# Clock.net
KiCad netlist of a schematic drawn in Altium Designer
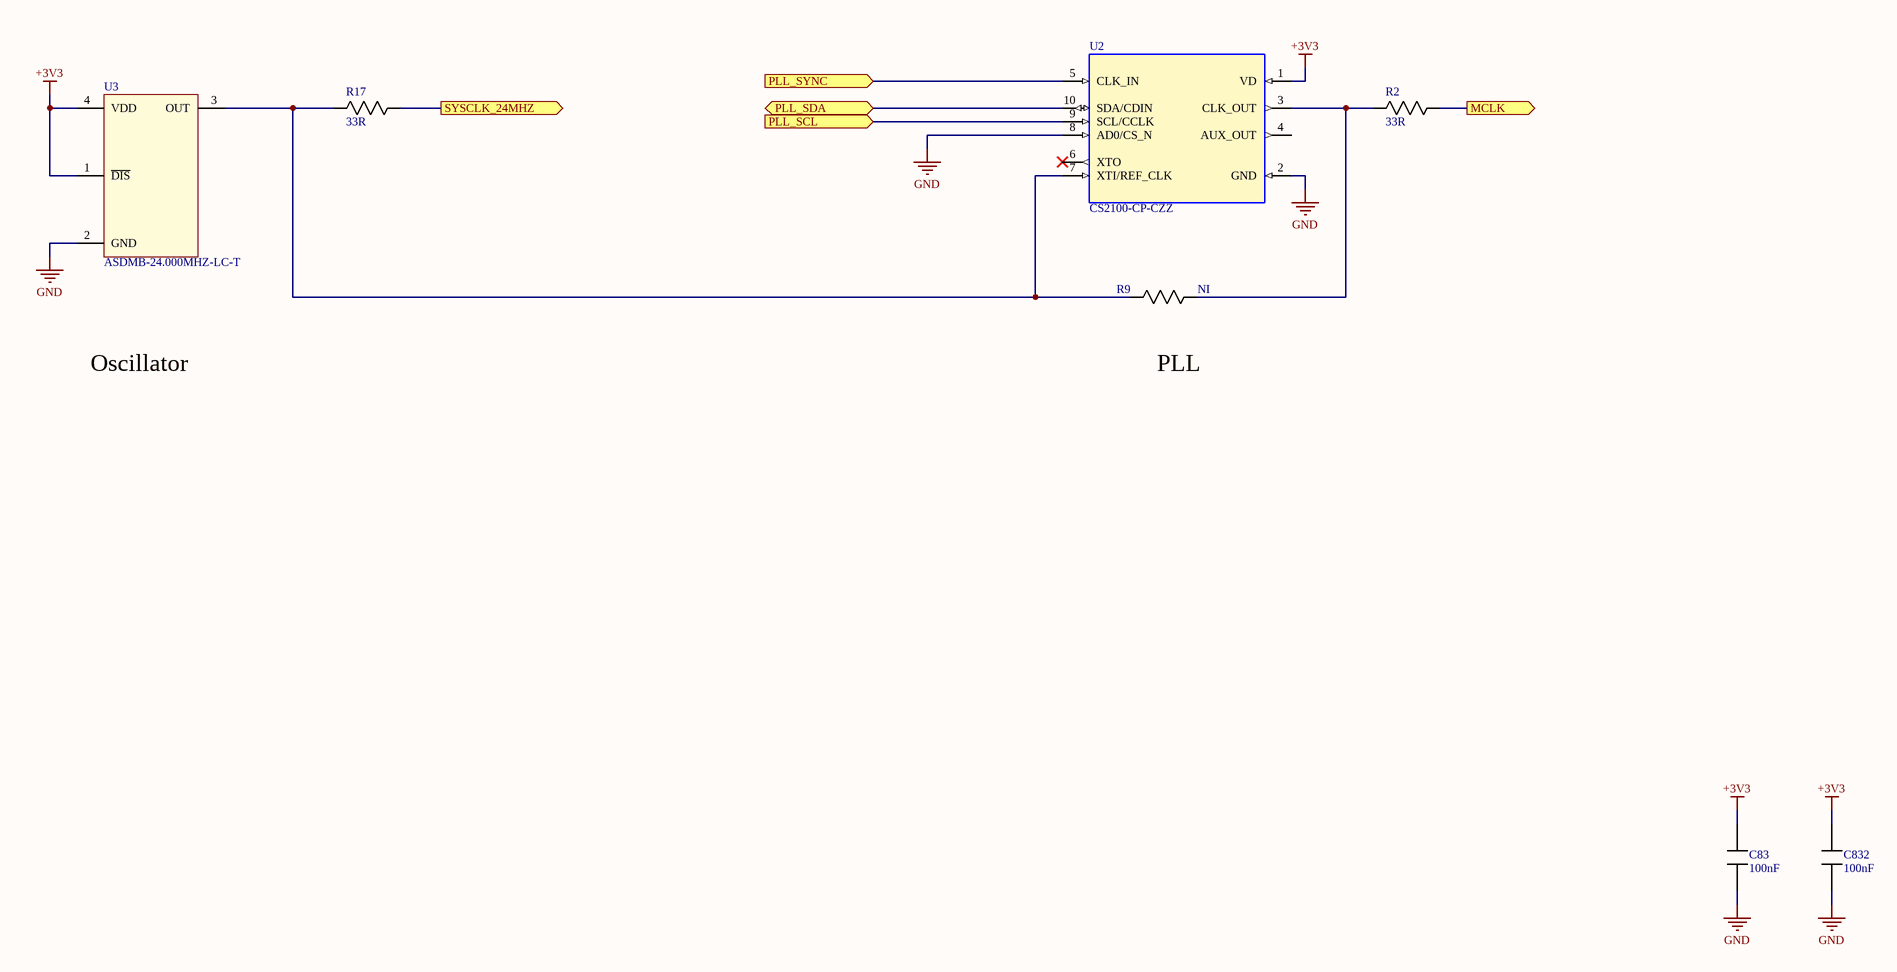
[diagram p0: Clock.SchDoc]

(export (version "E")
  (design (tool "Eeschema 10.0.6"))
  (components
    (comp (ref "C83")
      (value "100nF")
      (footprint "0603")
      (description "Capacitor")
      (fields (field (name "MFG") "Samsung"))
      (libsource (lib "INTER_2014") (part "Capacitor"))
    )
    (comp (ref "C832")
      (value "100nF")
      (footprint "0603")
      (description "Capacitor")
      (fields (field (name "MFG") "Samsung"))
      (libsource (lib "INTER_2014") (part "Capacitor"))
    )
    (comp (ref "R2")
      (value "33R")
      (footprint "0603")
      (description "Resistor")
      (fields (field (name "MFG") "Yageo"))
      (libsource (lib "INTER_2014") (part "Resistor"))
    )
    (comp (ref "R9")
      (value "Resistor")
      (footprint "0603")
      (fields (field (name "NI") "NI"))
      (libsource (lib "INTER_2014") (part "Resistor"))
    )
    (comp (ref "R17")
      (value "33R")
      (footprint "0603")
      (description "Resistor")
      (fields (field (name "MFG") "Yageo"))
      (libsource (lib "INTER_2014") (part "Resistor"))
    )
    (comp (ref "U2")
      (value "CS2100_CP")
      (footprint "MSOP10")
      (description "Fractional-N Clock Multiplier, Crystal Reference, MSOP10")
      (fields (field (name "MFG") "Cirrus Logic") (field (name "MFG_PN") "CS2100-CP-CZZ"))
      (libsource (lib "INTER_2014") (part "CS2100_CP"))
    )
    (comp (ref "U3")
      (value "OSC_ASDMB")
      (footprint "OSC_ADSMB")
      (description "Oscillator; 1V8 to 3V3")
      (fields (field (name "MFG") "Abracon") (field (name "MFG_PN") "ASDMB-24.000MHZ-LC-T"))
      (libsource (lib "INTER_2014") (part "OSC_ASDMB"))
    )
  )
  (nets
    (net (code "1") (name "+3V3") (class "Default")
      (node (ref "C83") (pin "1") (pintype "passive"))
      (node (ref "C832") (pin "1") (pintype "passive"))
      (node (ref "U2") (pin "1") (pinfunction "VD_1") (pintype "input"))
      (node (ref "U3") (pin "1") (pinfunction "~{DIS}_1") (pintype "passive"))
      (node (ref "U3") (pin "4") (pinfunction "VDD_4") (pintype "passive"))
    )
    (net (code "2") (name "/MCLK") (class "Default") (node (ref "R2") (pin "2") (pintype "passive")))
    (net (code "3") (name "/PLL_SCL") (class "Default")
      (node (ref "U2") (pin "9") (pinfunction "SCL/CCLK_9") (pintype "input"))
    )
    (net (code "4") (name "/PLL_SDA") (class "Default")
      (node (ref "U2") (pin "10") (pinfunction "SDA/CDIN_10") (pintype "bidirectional"))
    )
    (net (code "5") (name "/PLL_SYNC") (class "Default")
      (node (ref "U2") (pin "5") (pinfunction "CLK_IN_5") (pintype "input"))
    )
    (net (code "6") (name "/SYSCLK_24MHZ") (class "Default") (node (ref "R17") (pin "2") (pintype "passive")))
    (net (code "7") (name "GND") (class "Default")
      (node (ref "C83") (pin "2") (pintype "passive"))
      (node (ref "C832") (pin "2") (pintype "passive"))
      (node (ref "U2") (pin "2") (pinfunction "GND_2") (pintype "input"))
      (node (ref "U2") (pin "8") (pinfunction "AD0/CS_N_8") (pintype "input"))
      (node (ref "U3") (pin "2") (pinfunction "GND_2") (pintype "passive"))
    )
    (net (code "8") (name "Net-(U2-CLK_OUT)") (class "Default")
      (node (ref "R2") (pin "1") (pintype "passive"))
      (node (ref "R9") (pin "2") (pintype "passive"))
      (node (ref "U2") (pin "3") (pinfunction "CLK_OUT_3") (pintype "output"))
    )
    (net (code "9") (name "Net-(U2-XTI{slash}REF_CLK)") (class "Default")
      (node (ref "R17") (pin "1") (pintype "passive"))
      (node (ref "R9") (pin "1") (pintype "passive"))
      (node (ref "U2") (pin "7") (pinfunction "XTI/REF_CLK_7") (pintype "input"))
      (node (ref "U3") (pin "3") (pinfunction "OUT_3") (pintype "passive"))
    )
    (net (code "10") (name "unconnected-(U2-AUX_OUT-Pad4)") (class "Default")
      (node (ref "U2") (pin "4") (pinfunction "AUX_OUT_4") (pintype "output"))
    )
    (net (code "11") (name "unconnected-(U2-XTO-Pad6)") (class "Default")
      (node (ref "U2") (pin "6") (pinfunction "XTO_6") (pintype "output+no_connect"))
    )
  )
)
